# jphy_v1.net
KiCad netlist of a schematic drawn in EAGLE
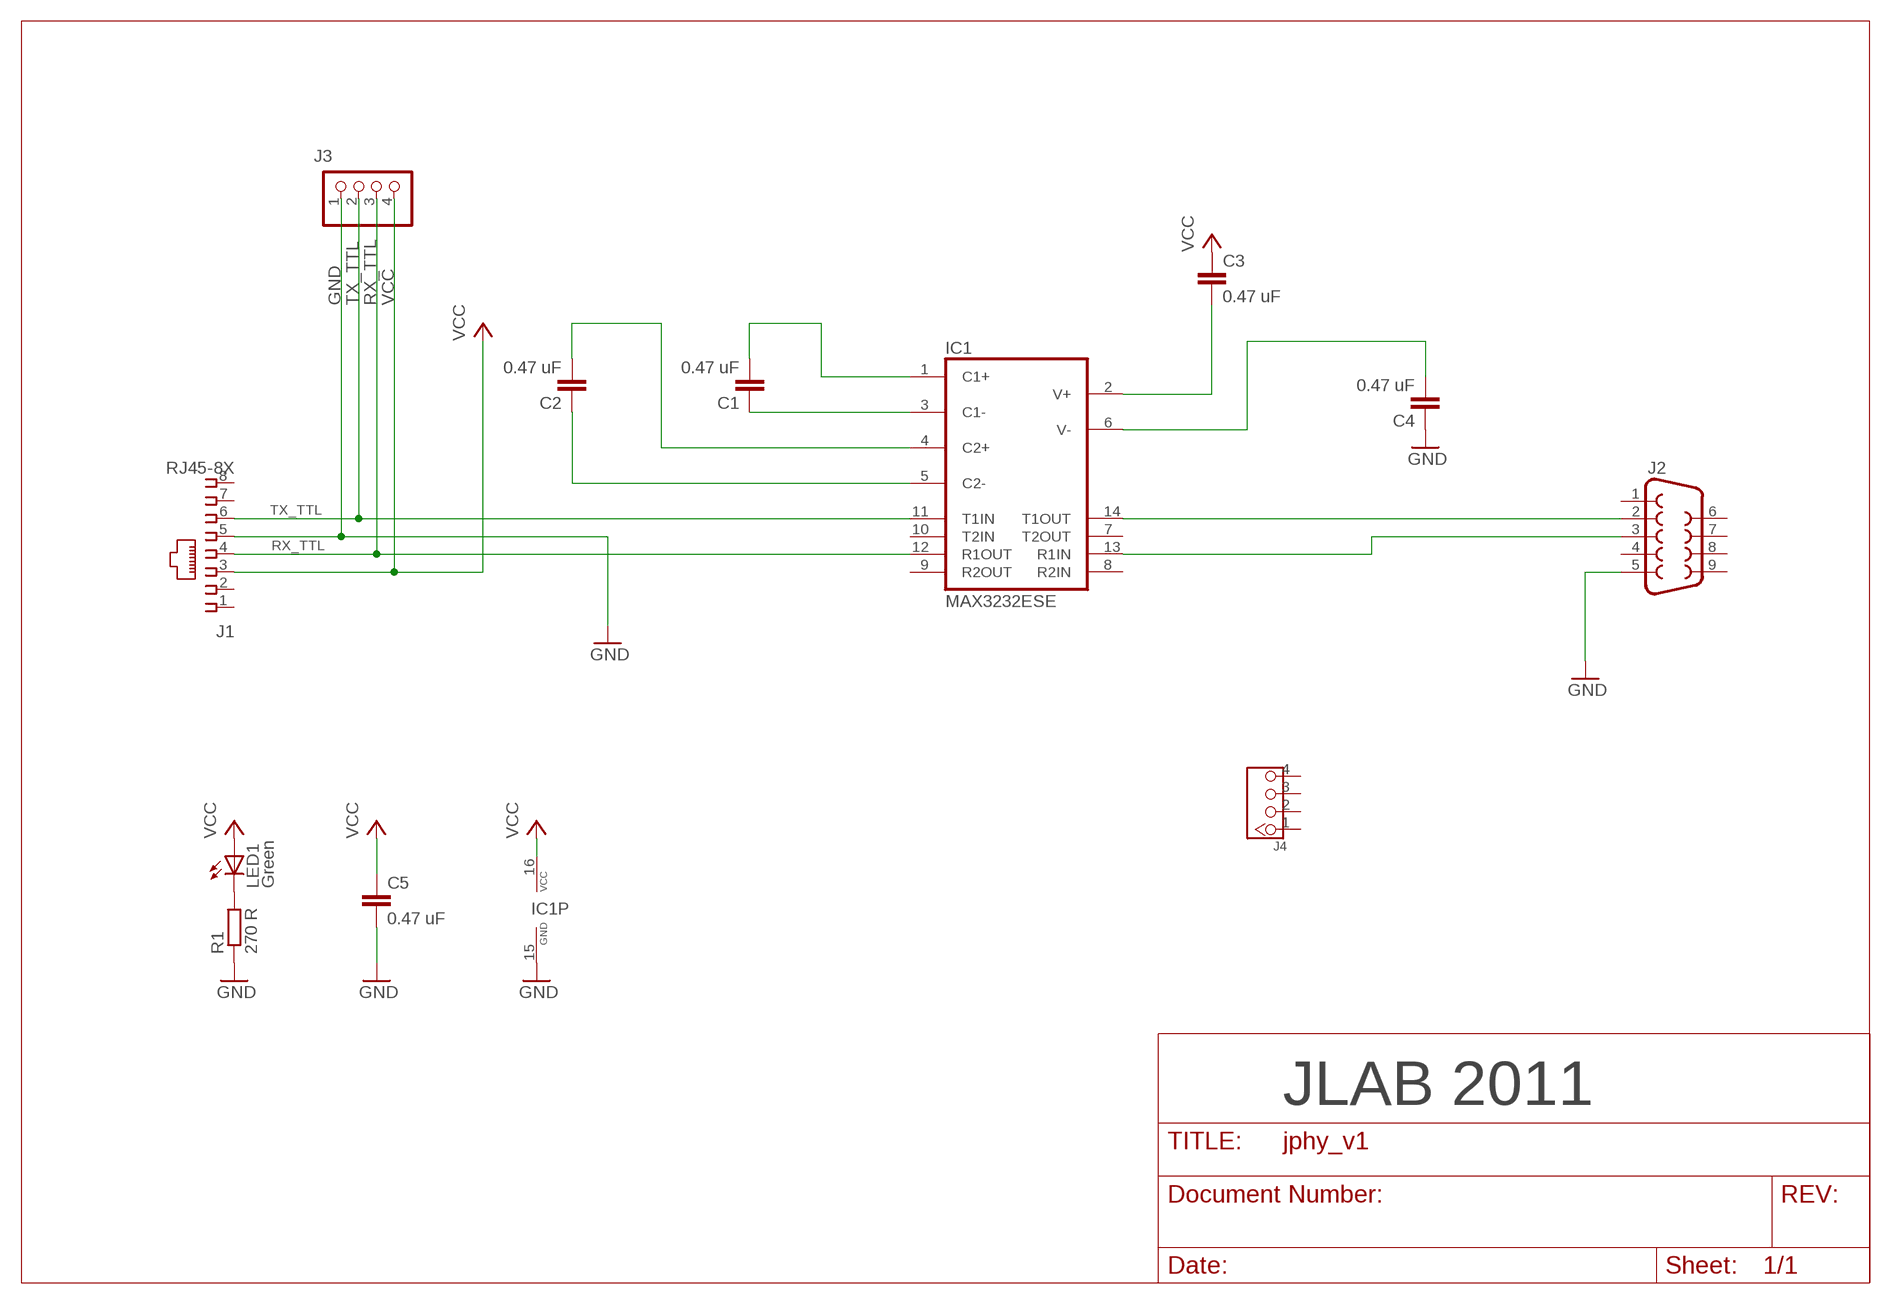
[diagram p0: schematic, sheet 1]

(export (version "E")
  (design (tool "Eeschema 10.0.6"))
  (components
    (comp (ref "C1")
      (value "0.47 uF")
      (footprint "eagle-import:C1206")
      (libsource (lib "eagle-import") (part "C-EUC1206"))
    )
    (comp (ref "C2")
      (value "0.47 uF")
      (footprint "eagle-import:C1206")
      (libsource (lib "eagle-import") (part "C-EUC1206"))
    )
    (comp (ref "C3")
      (value "0.47 uF")
      (footprint "eagle-import:C1206")
      (libsource (lib "eagle-import") (part "C-EUC1206"))
    )
    (comp (ref "C4")
      (value "0.47 uF")
      (footprint "eagle-import:C1206")
      (libsource (lib "eagle-import") (part "C-EUC1206"))
    )
    (comp (ref "C5")
      (value "0.47 uF")
      (footprint "eagle-import:C1206")
      (libsource (lib "eagle-import") (part "C-EUC1206"))
    )
    (comp (ref "IC1")
      (value "MAX3232ESE")
      (footprint "eagle-import:SO16")
      (fields (field (name "MF") "MAXIM"))
      (libsource (lib "eagle-import") (part "MAX3232SEE"))
    )
    (comp (ref "J1")
      (value "RJ45-8X")
      (footprint "eagle-import:RJ45-NO-SHIELD")
      (libsource (lib "eagle-import") (part "RJ45-8X"))
    )
    (comp (ref "J2")
      (value "F09D")
      (footprint "eagle-import:F09D")
      (libsource (lib "eagle-import") (part "F09D"))
    )
    (comp (ref "J3")
      (value "PINHD-1X4")
      (footprint "eagle-import:1X04")
      (libsource (lib "eagle-import") (part "PINHD-1X4"))
    )
    (comp (ref "J4")
      (value "HEADER-4P")
      (footprint "eagle-import:4P-2.54")
      (libsource (lib "eagle-import") (part "HEADER-4P"))
    )
    (comp (ref "LED1")
      (value "Green")
      (footprint "eagle-import:LED3MM")
      (libsource (lib "eagle-import") (part "LED3MM"))
    )
    (comp (ref "R1")
      (value "270 R")
      (footprint "eagle-import:0207_10")
      (libsource (lib "eagle-import") (part "R-EU_0207/10"))
    )
  )
  (nets
    (net (code "1") (name "/RX_TTL") (class "Default")
      (node (ref "IC1") (pin "12") (pinfunction "R1OUT_12") (pintype "output"))
      (node (ref "J1") (pin "4") (pinfunction "4_4") (pintype "passive"))
      (node (ref "J3") (pin "3") (pinfunction "3_3") (pintype "passive"))
    )
    (net (code "2") (name "/TX_TTL") (class "Default")
      (node (ref "IC1") (pin "11") (pinfunction "T1IN_11") (pintype "input"))
      (node (ref "J1") (pin "6") (pinfunction "6_6") (pintype "passive"))
      (node (ref "J3") (pin "2") (pinfunction "2_2") (pintype "passive"))
    )
    (net (code "3") (name "GND") (class "Default")
      (node (ref "C4") (pin "1") (pinfunction "1_1") (pintype "passive"))
      (node (ref "C5") (pin "2") (pinfunction "2_2") (pintype "passive"))
      (node (ref "IC1") (pin "15") (pinfunction "GND_15") (pintype "power_in"))
      (node (ref "J1") (pin "5") (pinfunction "5_5") (pintype "passive"))
      (node (ref "J2") (pin "5") (pinfunction "5_5") (pintype "passive"))
      (node (ref "J3") (pin "1") (pinfunction "1_1") (pintype "passive"))
      (node (ref "R1") (pin "1") (pinfunction "1_1") (pintype "passive"))
    )
    (net (code "4") (name "Net-(IC1A-C1+)") (class "Default")
      (node (ref "C1") (pin "2") (pinfunction "2_2") (pintype "passive"))
      (node (ref "IC1") (pin "1") (pinfunction "C1+_1") (pintype "bidirectional"))
    )
    (net (code "5") (name "Net-(IC1A-C1-)") (class "Default")
      (node (ref "C1") (pin "1") (pinfunction "1_1") (pintype "passive"))
      (node (ref "IC1") (pin "3") (pinfunction "C1-_3") (pintype "bidirectional"))
    )
    (net (code "6") (name "Net-(IC1A-C2+)") (class "Default")
      (node (ref "C2") (pin "2") (pinfunction "2_2") (pintype "passive"))
      (node (ref "IC1") (pin "4") (pinfunction "C2+_4") (pintype "bidirectional"))
    )
    (net (code "7") (name "Net-(IC1A-C2-)") (class "Default")
      (node (ref "C2") (pin "1") (pinfunction "1_1") (pintype "passive"))
      (node (ref "IC1") (pin "5") (pinfunction "C2-_5") (pintype "bidirectional"))
    )
    (net (code "8") (name "Net-(IC1A-R1IN)") (class "Default")
      (node (ref "IC1") (pin "13") (pinfunction "R1IN_13") (pintype "input"))
      (node (ref "J2") (pin "3") (pinfunction "3_3") (pintype "passive"))
    )
    (net (code "9") (name "Net-(IC1A-T1OUT)") (class "Default")
      (node (ref "IC1") (pin "14") (pinfunction "T1OUT_14") (pintype "output"))
      (node (ref "J2") (pin "2") (pinfunction "2_2") (pintype "passive"))
    )
    (net (code "10") (name "Net-(IC1A-V+)") (class "Default")
      (node (ref "C3") (pin "2") (pinfunction "2_2") (pintype "passive"))
      (node (ref "IC1") (pin "2") (pinfunction "V+_2") (pintype "bidirectional"))
    )
    (net (code "11") (name "Net-(IC1A-V-)") (class "Default")
      (node (ref "C4") (pin "2") (pinfunction "2_2") (pintype "passive"))
      (node (ref "IC1") (pin "6") (pinfunction "V-_6") (pintype "bidirectional"))
    )
    (net (code "12") (name "Net-(LED1-C)") (class "Default")
      (node (ref "LED1") (pin "K") (pinfunction "C_K") (pintype "passive"))
      (node (ref "R1") (pin "2") (pinfunction "2_2") (pintype "passive"))
    )
    (net (code "13") (name "VCC") (class "Default")
      (node (ref "C3") (pin "1") (pinfunction "1_1") (pintype "passive"))
      (node (ref "C5") (pin "1") (pinfunction "1_1") (pintype "passive"))
      (node (ref "IC1") (pin "16") (pinfunction "VCC_16") (pintype "power_in"))
      (node (ref "J1") (pin "3") (pinfunction "3_3") (pintype "passive"))
      (node (ref "J3") (pin "4") (pinfunction "4_4") (pintype "passive"))
      (node (ref "LED1") (pin "A") (pinfunction "A_A") (pintype "passive"))
    )
    (net (code "14") (name "unconnected-(IC1A-R2IN-Pad8)") (class "Default")
      (node (ref "IC1") (pin "8") (pinfunction "R2IN_8") (pintype "input"))
    )
    (net (code "15") (name "unconnected-(IC1A-R2OUT-Pad9)") (class "Default")
      (node (ref "IC1") (pin "9") (pinfunction "R2OUT_9") (pintype "output"))
    )
    (net (code "16") (name "unconnected-(IC1A-T2IN-Pad10)") (class "Default")
      (node (ref "IC1") (pin "10") (pinfunction "T2IN_10") (pintype "input"))
    )
    (net (code "17") (name "unconnected-(IC1A-T2OUT-Pad7)") (class "Default")
      (node (ref "IC1") (pin "7") (pinfunction "T2OUT_7") (pintype "output"))
    )
    (net (code "18") (name "unconnected-(J1-Pad1)") (class "Default")
      (node (ref "J1") (pin "1") (pinfunction "1_1") (pintype "passive"))
    )
    (net (code "19") (name "unconnected-(J1-Pad2)") (class "Default")
      (node (ref "J1") (pin "2") (pinfunction "2_2") (pintype "passive"))
    )
    (net (code "20") (name "unconnected-(J1-Pad7)") (class "Default")
      (node (ref "J1") (pin "7") (pinfunction "7_7") (pintype "passive"))
    )
    (net (code "21") (name "unconnected-(J1-Pad8)") (class "Default")
      (node (ref "J1") (pin "8") (pinfunction "8_8") (pintype "passive"))
    )
    (net (code "22") (name "unconnected-(J2-Pad1)") (class "Default")
      (node (ref "J2") (pin "1") (pinfunction "1_1") (pintype "passive"))
    )
    (net (code "23") (name "unconnected-(J2-Pad4)") (class "Default")
      (node (ref "J2") (pin "4") (pinfunction "4_4") (pintype "passive"))
    )
    (net (code "24") (name "unconnected-(J2-Pad6)") (class "Default")
      (node (ref "J2") (pin "6") (pinfunction "6_6") (pintype "passive"))
    )
    (net (code "25") (name "unconnected-(J2-Pad7)") (class "Default")
      (node (ref "J2") (pin "7") (pinfunction "7_7") (pintype "passive"))
    )
    (net (code "26") (name "unconnected-(J2-Pad8)") (class "Default")
      (node (ref "J2") (pin "8") (pinfunction "8_8") (pintype "passive"))
    )
    (net (code "27") (name "unconnected-(J2-Pad9)") (class "Default")
      (node (ref "J2") (pin "9") (pinfunction "9_9") (pintype "passive"))
    )
    (net (code "28") (name "unconnected-(J4-P$1-Pad1)") (class "Default")
      (node (ref "J4") (pin "1") (pinfunction "P$1_1") (pintype "bidirectional"))
    )
    (net (code "29") (name "unconnected-(J4-P$2-Pad2)") (class "Default")
      (node (ref "J4") (pin "2") (pinfunction "P$2_2") (pintype "bidirectional"))
    )
    (net (code "30") (name "unconnected-(J4-P$3-Pad3)") (class "Default")
      (node (ref "J4") (pin "3") (pinfunction "P$3_3") (pintype "bidirectional"))
    )
    (net (code "31") (name "unconnected-(J4-P$4-Pad4)") (class "Default")
      (node (ref "J4") (pin "4") (pinfunction "P$4_4") (pintype "bidirectional"))
    )
  )
)
